# adcbuttons.net
KiCad netlist of a schematic drawn in EAGLE
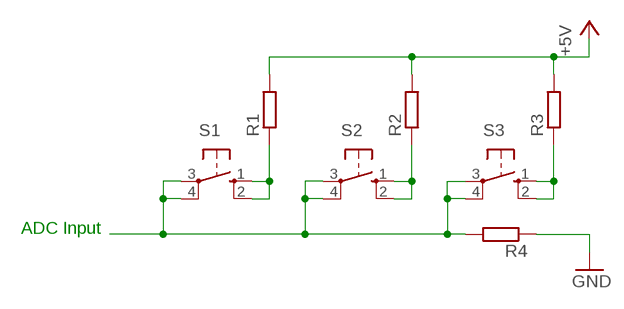
[diagram p0: schematic, sheet 1]

(export (version "E")
  (design (tool "Eeschema 10.0.6"))
  (components
    (comp (ref "R1")
      (value "R-EU_0309/10")
      (footprint "eagle-import:0309_10")
      (libsource (lib "eagle-import") (part "R-EU_0309/10"))
    )
    (comp (ref "R2")
      (value "R-EU_0309/10")
      (footprint "eagle-import:0309_10")
      (libsource (lib "eagle-import") (part "R-EU_0309/10"))
    )
    (comp (ref "R3")
      (value "R-EU_0309/10")
      (footprint "eagle-import:0309_10")
      (libsource (lib "eagle-import") (part "R-EU_0309/10"))
    )
    (comp (ref "R4")
      (value "R-EU_0309/10")
      (footprint "eagle-import:0309_10")
      (libsource (lib "eagle-import") (part "R-EU_0309/10"))
    )
    (comp (ref "S1")
      (value "10-XX")
      (footprint "eagle-import:B3F-10XX")
      (fields (field (name "MPN") "B3F-1000"))
      (libsource (lib "eagle-import") (part "10-XX"))
    )
    (comp (ref "S2")
      (value "10-XX")
      (footprint "eagle-import:B3F-10XX")
      (fields (field (name "MPN") "B3F-1000"))
      (libsource (lib "eagle-import") (part "10-XX"))
    )
    (comp (ref "S3")
      (value "10-XX")
      (footprint "eagle-import:B3F-10XX")
      (fields (field (name "MPN") "B3F-1000"))
      (libsource (lib "eagle-import") (part "10-XX"))
    )
  )
  (nets
    (net (code "1") (name "+5V") (class "Default")
      (node (ref "R1") (pin "2") (pinfunction "2_2") (pintype "passive"))
      (node (ref "R2") (pin "2") (pinfunction "2_2") (pintype "passive"))
      (node (ref "R3") (pin "2") (pinfunction "2_2") (pintype "passive"))
    )
    (net (code "2") (name "GND") (class "Default")
      (node (ref "R4") (pin "1") (pinfunction "1_1") (pintype "passive"))
    )
    (net (code "3") (name "Net-(S1-P)") (class "Default")
      (node (ref "R4") (pin "2") (pinfunction "2_2") (pintype "passive"))
      (node (ref "S1") (pin "3") (pinfunction "P_3") (pintype "passive"))
      (node (ref "S1") (pin "4") (pinfunction "P1_4") (pintype "passive"))
      (node (ref "S2") (pin "3") (pinfunction "P_3") (pintype "passive"))
      (node (ref "S2") (pin "4") (pinfunction "P1_4") (pintype "passive"))
      (node (ref "S3") (pin "3") (pinfunction "P_3") (pintype "passive"))
      (node (ref "S3") (pin "4") (pinfunction "P1_4") (pintype "passive"))
    )
    (net (code "4") (name "Net-(S1-S)") (class "Default")
      (node (ref "R1") (pin "1") (pinfunction "1_1") (pintype "passive"))
      (node (ref "S1") (pin "1") (pinfunction "S_1") (pintype "passive"))
      (node (ref "S1") (pin "2") (pinfunction "S1_2") (pintype "passive"))
    )
    (net (code "5") (name "Net-(S2-S)") (class "Default")
      (node (ref "R2") (pin "1") (pinfunction "1_1") (pintype "passive"))
      (node (ref "S2") (pin "1") (pinfunction "S_1") (pintype "passive"))
      (node (ref "S2") (pin "2") (pinfunction "S1_2") (pintype "passive"))
    )
    (net (code "6") (name "Net-(S3-S)") (class "Default")
      (node (ref "R3") (pin "1") (pinfunction "1_1") (pintype "passive"))
      (node (ref "S3") (pin "1") (pinfunction "S_1") (pintype "passive"))
      (node (ref "S3") (pin "2") (pinfunction "S1_2") (pintype "passive"))
    )
  )
)
